# bi-directional_mosfet_level_shifter.net
KiCad netlist of a schematic drawn in EAGLE
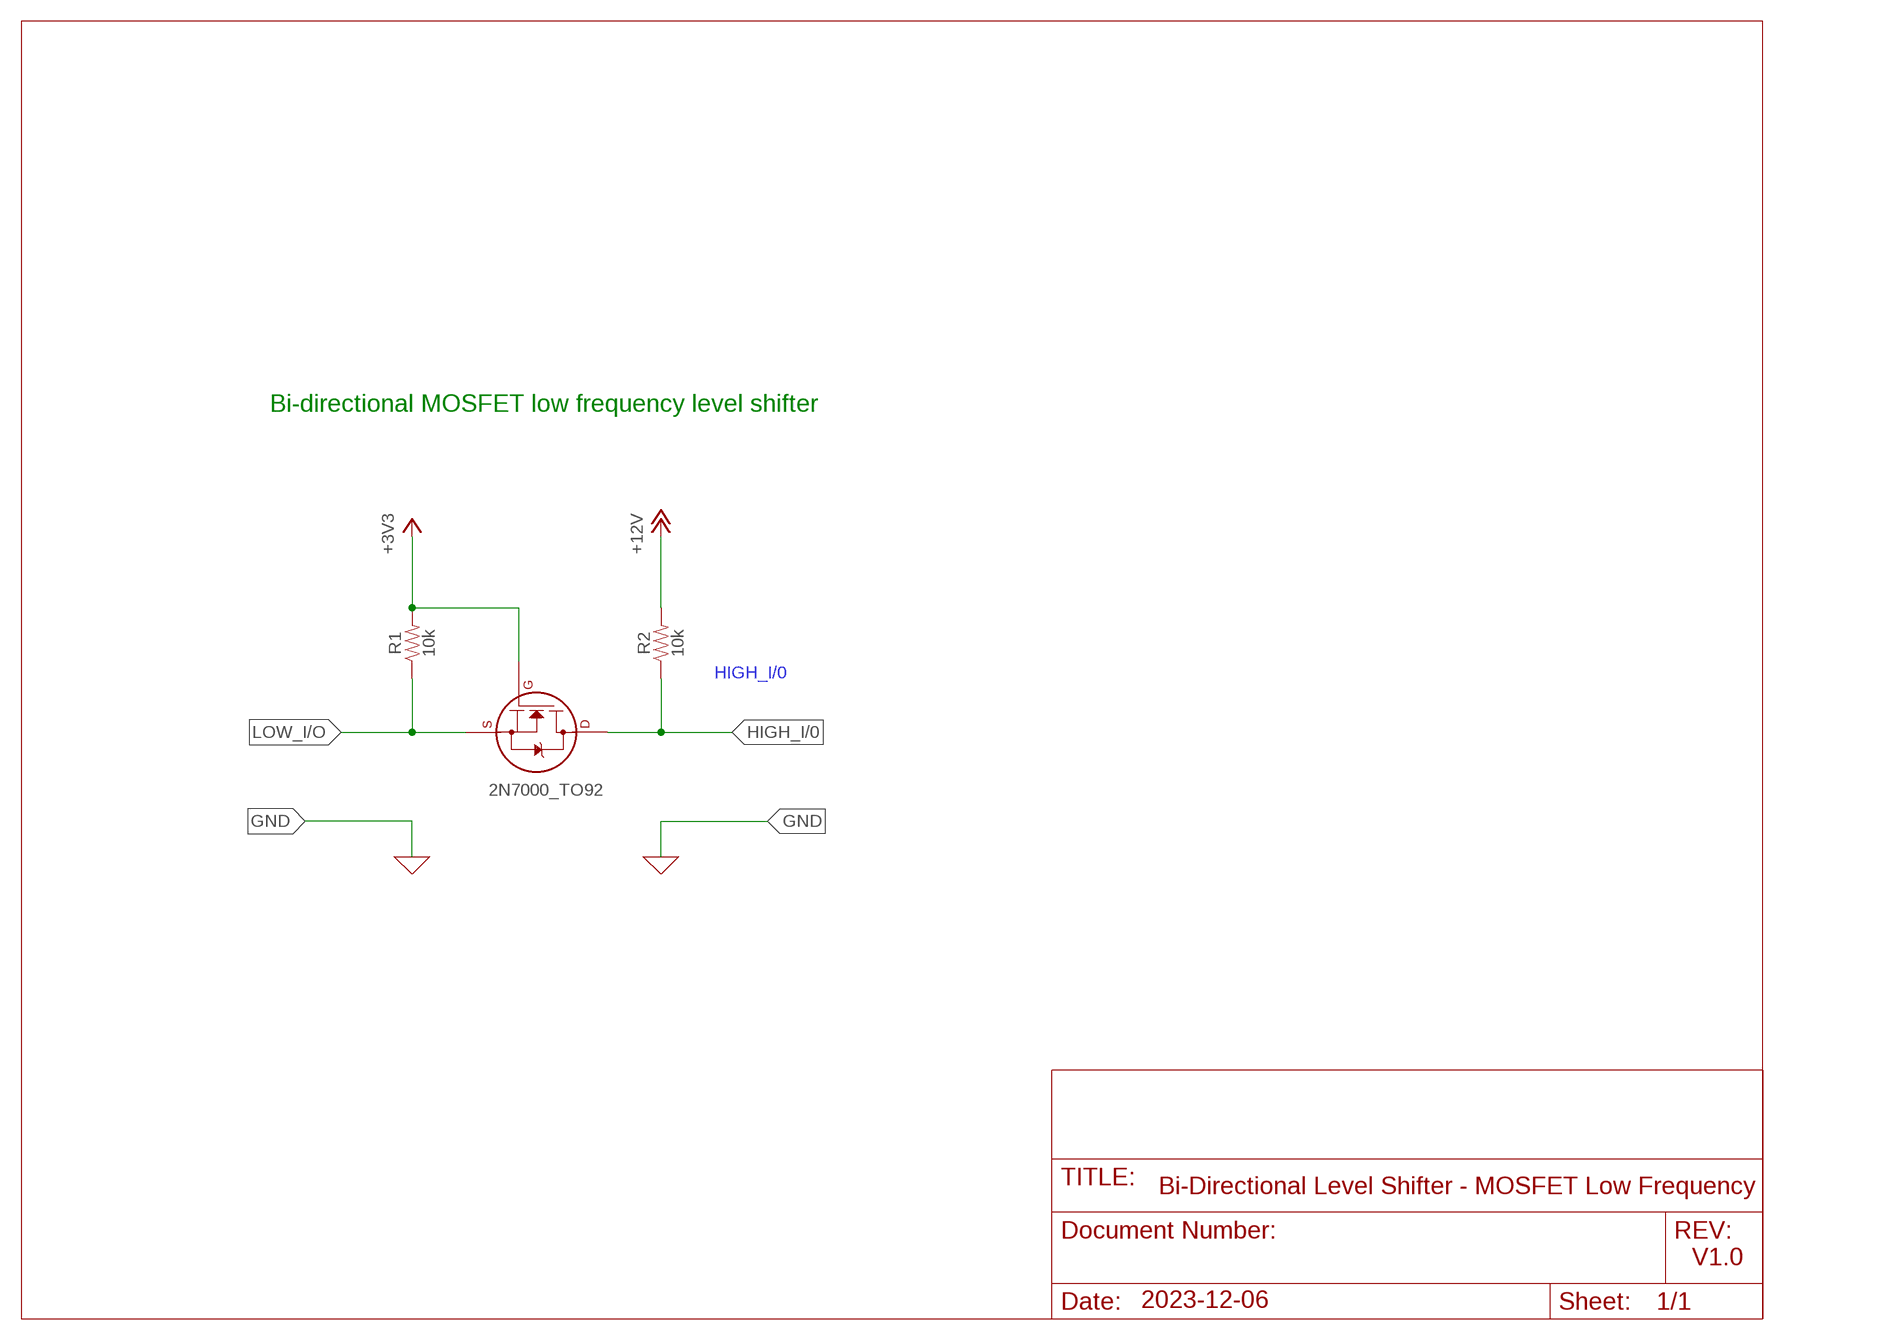
[diagram p0: schematic, sheet 1]

(export (version "E")
  (design (tool "Eeschema 10.0.6"))
  (components
    (comp (ref "2N7000_TO92")
      (value "2N7000_TO92")
      (footprint "eagle-import:TO-92")
      (libsource (lib "eagle-import") (part "2N700_TO920"))
    )
    (comp (ref "R1")
      (value "10k")
      (footprint "eagle-import:AXIAL-0.3-KIT")
      (libsource (lib "eagle-import") (part "10KOHM-HORIZ_KIT-1/4W-1%"))
    )
    (comp (ref "R2")
      (value "10k")
      (footprint "eagle-import:AXIAL-0.3-KIT")
      (libsource (lib "eagle-import") (part "10KOHM-HORIZ_KIT-1/4W-1%"))
    )
  )
  (nets
    (net (code "1") (name "+3V3") (class "Default")
      (node (ref "2N7000_TO92") (pin "2") (pinfunction "G_2") (pintype "tri_state"))
      (node (ref "R1") (pin "P$2") (pinfunction "2_P$2") (pintype "passive"))
    )
    (net (code "2") (name "+12V") (class "Default")
      (node (ref "R2") (pin "P$2") (pinfunction "2_P$2") (pintype "passive"))
    )
    (net (code "4") (name "HIGH_I{slash}0") (class "Default")
      (node (ref "2N7000_TO92") (pin "3") (pinfunction "D_3") (pintype "bidirectional"))
      (node (ref "R2") (pin "P$1") (pinfunction "1_P$1") (pintype "passive"))
    )
    (net (code "5") (name "LOW_I{slash}O") (class "Default")
      (node (ref "2N7000_TO92") (pin "1") (pinfunction "S_1") (pintype "bidirectional"))
      (node (ref "R1") (pin "P$1") (pinfunction "1_P$1") (pintype "passive"))
    )
  )
)
